# DCCInterface.net
KiCad netlist of a schematic drawn in EAGLE
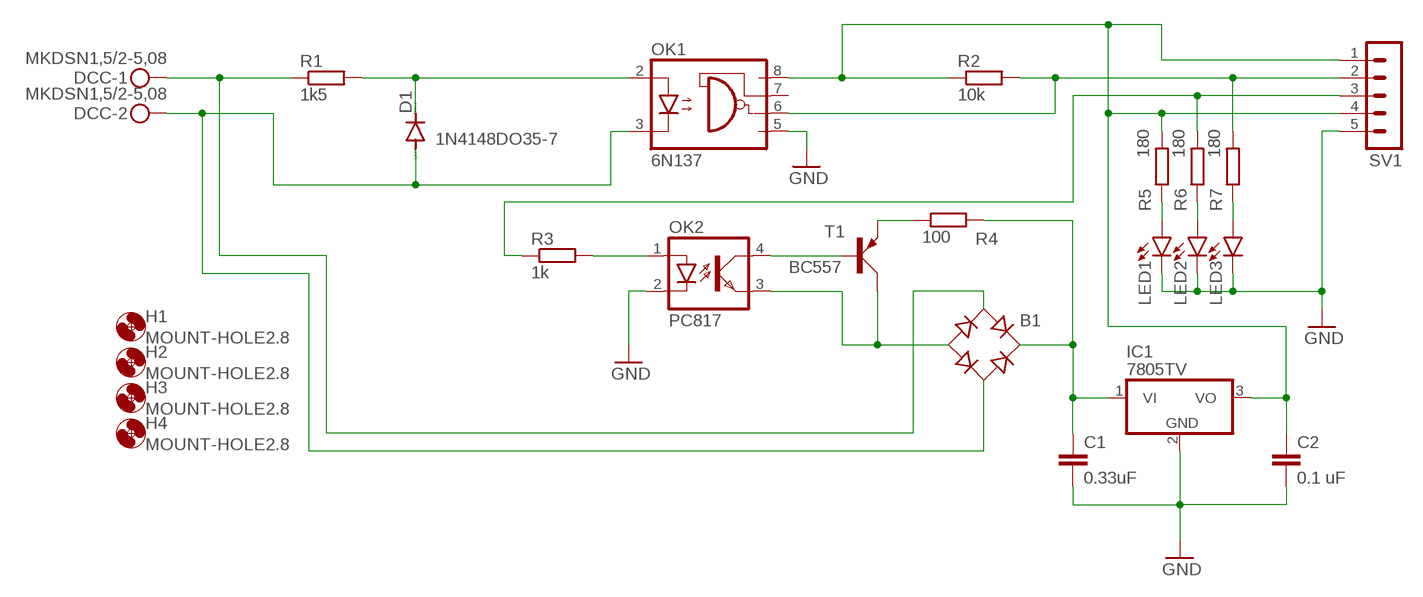
[diagram p0: schematic, sheet 1]

(export (version "E")
  (design (tool "Eeschema 10.0.6"))
  (components
    (comp (ref "B1")
      (value "RB1A")
      (footprint "eagle-import:RB1A")
      (libsource (lib "eagle-import") (part "RB1A"))
    )
    (comp (ref "C1")
      (value "0.33uF")
      (footprint "eagle-import:C025-025X050")
      (libsource (lib "eagle-import") (part "C-EU025-025X050"))
    )
    (comp (ref "C2")
      (value "0.1 uF")
      (footprint "eagle-import:C025-025X050")
      (libsource (lib "eagle-import") (part "C-EU025-025X050"))
    )
    (comp (ref "D1")
      (value "1N4148DO35-7")
      (footprint "eagle-import:DO35-7")
      (libsource (lib "eagle-import") (part "1N4148DO35-7"))
    )
    (comp (ref "DCC")
      (value "MKDSN1,5/2-5,08")
      (footprint "eagle-import:MKDSN1,5_2-5,08")
      (libsource (lib "eagle-import") (part "MKDSN1,5/2-5,08"))
    )
    (comp (ref "H1")
      (value "MOUNT-HOLE2.8")
      (footprint "eagle-import:2,8")
      (libsource (lib "eagle-import") (part "MOUNT-HOLE2.8"))
    )
    (comp (ref "H2")
      (value "MOUNT-HOLE2.8")
      (footprint "eagle-import:2,8")
      (libsource (lib "eagle-import") (part "MOUNT-HOLE2.8"))
    )
    (comp (ref "H3")
      (value "MOUNT-HOLE2.8")
      (footprint "eagle-import:2,8")
      (libsource (lib "eagle-import") (part "MOUNT-HOLE2.8"))
    )
    (comp (ref "H4")
      (value "MOUNT-HOLE2.8")
      (footprint "eagle-import:2,8")
      (libsource (lib "eagle-import") (part "MOUNT-HOLE2.8"))
    )
    (comp (ref "IC1")
      (value "7805TV")
      (footprint "eagle-import:TO220V")
      (libsource (lib "eagle-import") (part "78TV05"))
    )
    (comp (ref "LED1")
      (value "LED3MM")
      (footprint "eagle-import:LED3MM")
      (libsource (lib "eagle-import") (part "LED3MM"))
    )
    (comp (ref "LED2")
      (value "LED3MM")
      (footprint "eagle-import:LED3MM")
      (libsource (lib "eagle-import") (part "LED3MM"))
    )
    (comp (ref "LED3")
      (value "LED3MM")
      (footprint "eagle-import:LED3MM")
      (libsource (lib "eagle-import") (part "LED3MM"))
    )
    (comp (ref "OK1")
      (value "6N137")
      (footprint "eagle-import:DIL08")
      (libsource (lib "eagle-import") (part "6N137"))
    )
    (comp (ref "OK2")
      (value "PC817")
      (footprint "eagle-import:DIL04")
      (fields (field (name "MPN") "PC817X4J000F"))
      (libsource (lib "eagle-import") (part "PC817"))
    )
    (comp (ref "R1")
      (value "1k5")
      (footprint "eagle-import:0204_7")
      (libsource (lib "eagle-import") (part "R-EU_0204/7"))
    )
    (comp (ref "R2")
      (value "10k")
      (footprint "eagle-import:0204_7")
      (libsource (lib "eagle-import") (part "R-EU_0204/7"))
    )
    (comp (ref "R3")
      (value "1k")
      (footprint "eagle-import:0204_7")
      (libsource (lib "eagle-import") (part "R-EU_0204/7"))
    )
    (comp (ref "R4")
      (value "100")
      (footprint "eagle-import:0204_7")
      (libsource (lib "eagle-import") (part "R-EU_0204/7"))
    )
    (comp (ref "R5")
      (value "180")
      (footprint "eagle-import:0204_7")
      (libsource (lib "eagle-import") (part "R-EU_0204/7"))
    )
    (comp (ref "R6")
      (value "180")
      (footprint "eagle-import:0204_7")
      (libsource (lib "eagle-import") (part "R-EU_0204/7"))
    )
    (comp (ref "R7")
      (value "180")
      (footprint "eagle-import:0204_7")
      (libsource (lib "eagle-import") (part "R-EU_0204/7"))
    )
    (comp (ref "SV1")
      (value "MA05-1")
      (footprint "eagle-import:MA05-1")
      (libsource (lib "eagle-import") (part "MA05-1"))
    )
    (comp (ref "T1")
      (value "BC557")
      (footprint "eagle-import:SOT54A")
      (libsource (lib "eagle-import") (part "BC557"))
    )
  )
  (nets
    (net (code "1") (name "GND") (class "Default")
      (node (ref "C1") (pin "2") (pinfunction "2_2") (pintype "passive"))
      (node (ref "C2") (pin "2") (pinfunction "2_2") (pintype "passive"))
      (node (ref "IC1") (pin "2") (pinfunction "GND_2") (pintype "passive"))
      (node (ref "LED1") (pin "K") (pinfunction "C_K") (pintype "passive"))
      (node (ref "LED2") (pin "K") (pinfunction "C_K") (pintype "passive"))
      (node (ref "LED3") (pin "K") (pinfunction "C_K") (pintype "passive"))
      (node (ref "OK1") (pin "5") (pinfunction "GND_5") (pintype "passive"))
      (node (ref "OK2") (pin "2") (pinfunction "C_2") (pintype "passive"))
      (node (ref "SV1") (pin "5") (pinfunction "5_5") (pintype "passive"))
    )
    (net (code "2") (name "Net-(DCCA-KL)") (class "Default")
      (node (ref "B1") (pin "AC1") (pinfunction "AC1_AC1") (pintype "passive"))
      (node (ref "DCC") (pin "1") (pinfunction "KL_1") (pintype "passive"))
      (node (ref "R1") (pin "1") (pinfunction "1_1") (pintype "passive"))
    )
    (net (code "3") (name "Net-(DCCB-KL)") (class "Default")
      (node (ref "B1") (pin "AC2") (pinfunction "AC2_AC2") (pintype "passive"))
      (node (ref "D1") (pin "A") (pinfunction "A_A") (pintype "passive"))
      (node (ref "DCC") (pin "2") (pinfunction "KL_2") (pintype "passive"))
      (node (ref "OK1") (pin "3") (pinfunction "C_3") (pintype "passive"))
    )
    (net (code "4") (name "Net-(IC1-VI)") (class "Default")
      (node (ref "B1") (pin "+") (pinfunction "+_+") (pintype "passive"))
      (node (ref "C1") (pin "1") (pinfunction "1_1") (pintype "passive"))
      (node (ref "IC1") (pin "1") (pinfunction "VI_1") (pintype "input"))
      (node (ref "R4") (pin "2") (pinfunction "2_2") (pintype "passive"))
    )
    (net (code "5") (name "Net-(IC1-VO)") (class "Default")
      (node (ref "C2") (pin "1") (pinfunction "1_1") (pintype "passive"))
      (node (ref "IC1") (pin "3") (pinfunction "VO_3") (pintype "passive"))
      (node (ref "OK1") (pin "8") (pinfunction "VCC_8") (pintype "passive"))
      (node (ref "R2") (pin "1") (pinfunction "1_1") (pintype "passive"))
      (node (ref "R5") (pin "2") (pinfunction "2_2") (pintype "passive"))
      (node (ref "SV1") (pin "1") (pinfunction "1_1") (pintype "passive"))
      (node (ref "SV1") (pin "4") (pinfunction "4_4") (pintype "passive"))
    )
    (net (code "6") (name "Net-(LED1-PadA)") (class "Default")
      (node (ref "LED1") (pin "A") (pinfunction "A_A") (pintype "passive"))
      (node (ref "R5") (pin "1") (pinfunction "1_1") (pintype "passive"))
    )
    (net (code "7") (name "Net-(LED2-PadA)") (class "Default")
      (node (ref "LED2") (pin "A") (pinfunction "A_A") (pintype "passive"))
      (node (ref "R6") (pin "1") (pinfunction "1_1") (pintype "passive"))
    )
    (net (code "8") (name "Net-(LED3-PadA)") (class "Default")
      (node (ref "LED3") (pin "A") (pinfunction "A_A") (pintype "passive"))
      (node (ref "R7") (pin "1") (pinfunction "1_1") (pintype "passive"))
    )
    (net (code "9") (name "Net-(OK1-A)") (class "Default")
      (node (ref "D1") (pin "C") (pinfunction "C_C") (pintype "passive"))
      (node (ref "OK1") (pin "2") (pinfunction "A_2") (pintype "passive"))
      (node (ref "R1") (pin "2") (pinfunction "2_2") (pintype "passive"))
    )
    (net (code "10") (name "Net-(OK1-VO)") (class "Default")
      (node (ref "OK1") (pin "6") (pinfunction "VO_6") (pintype "passive"))
      (node (ref "R2") (pin "2") (pinfunction "2_2") (pintype "passive"))
      (node (ref "R7") (pin "2") (pinfunction "2_2") (pintype "passive"))
      (node (ref "SV1") (pin "2") (pinfunction "2_2") (pintype "passive"))
    )
    (net (code "11") (name "Net-(OK2-A)") (class "Default")
      (node (ref "OK2") (pin "1") (pinfunction "A_1") (pintype "passive"))
      (node (ref "R3") (pin "2") (pinfunction "2_2") (pintype "passive"))
    )
    (net (code "12") (name "Net-(OK2-COL)") (class "Default")
      (node (ref "OK2") (pin "4") (pinfunction "COL_4") (pintype "passive"))
      (node (ref "T1") (pin "B") (pinfunction "B_B") (pintype "passive"))
    )
    (net (code "13") (name "Net-(OK2-EMIT)") (class "Default")
      (node (ref "B1") (pin "-") (pinfunction "-_-") (pintype "passive"))
      (node (ref "OK2") (pin "3") (pinfunction "EMIT_3") (pintype "passive"))
      (node (ref "T1") (pin "C") (pinfunction "C_C") (pintype "passive"))
    )
    (net (code "14") (name "Net-(R3-Pad1)") (class "Default")
      (node (ref "R3") (pin "1") (pinfunction "1_1") (pintype "passive"))
      (node (ref "R6") (pin "2") (pinfunction "2_2") (pintype "passive"))
      (node (ref "SV1") (pin "3") (pinfunction "3_3") (pintype "passive"))
    )
    (net (code "15") (name "Net-(R4-Pad1)") (class "Default")
      (node (ref "R4") (pin "1") (pinfunction "1_1") (pintype "passive"))
      (node (ref "T1") (pin "E") (pinfunction "E_E") (pintype "passive"))
    )
    (net (code "16") (name "unconnected-(OK1-VE-Pad7)") (class "Default")
      (node (ref "OK1") (pin "7") (pinfunction "VE_7") (pintype "passive"))
    )
  )
)
